# Sheet1.net
KiCad netlist of a schematic drawn in Altium Designer
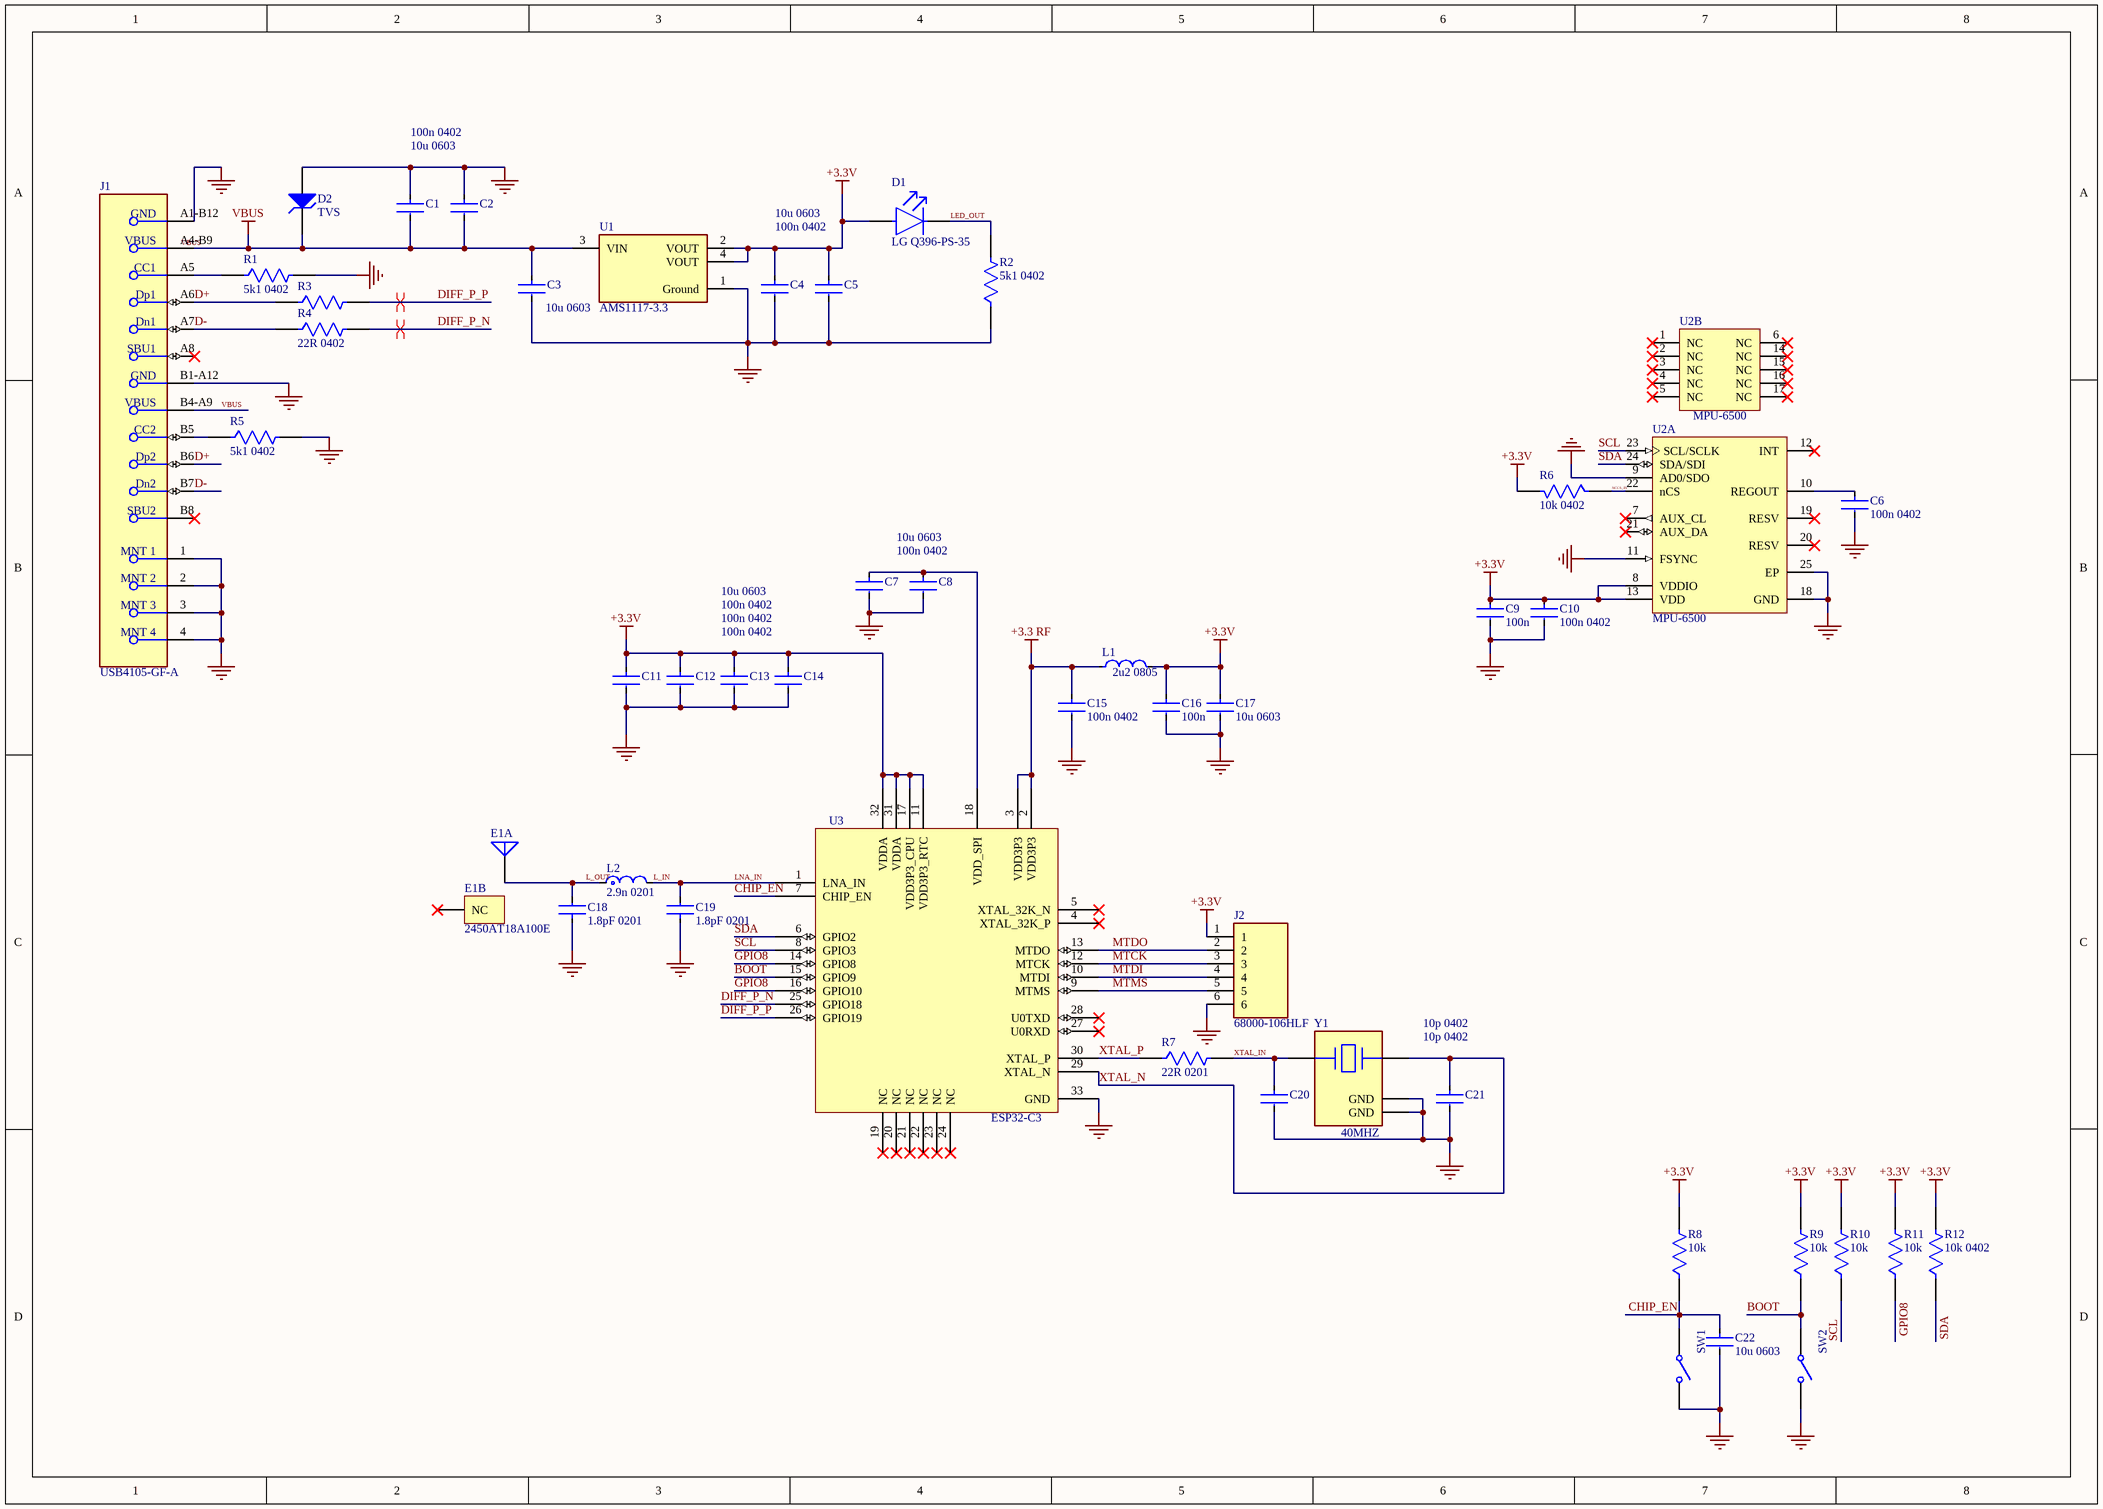
[diagram p0: Sheet1.SchDoc]

(export (version "E")
  (design (tool "Eeschema 10.0.6"))
  (components
    (comp (ref "C1")
      (value "100n 0402")
      (footprint "FP-0402B104K500CT-IPC_C")
      (description "CAP CER 0.1UF 50V X7R 0402")
      (fields (field (name "TOLERANCE") "10%"))
      (libsource (lib "Altium Content Vault") (part "11868f565c42a9108669ba33697ecf6"))
    )
    (comp (ref "C2")
      (value "10u 0603")
      (footprint "FP-GRM188-0_15-IPC_C")
      (description "Chip Multilayer Ceramic Capacitors for General Purpose, 0603, 10uF, X5R, 15%, 20%, 16V")
      (fields (field (name "TOLERANCE") "20%"))
      (libsource (lib "Altium Content Vault") (part "02cd4be3c70576c341d710602a673aa"))
    )
    (comp (ref "C3")
      (value "10u 0603")
      (footprint "FP-GRM188-0_15-IPC_C")
      (description "Chip Multilayer Ceramic Capacitors for General Purpose, 0603, 10uF, X5R, 15%, 20%, 16V")
      (fields (field (name "TOLERANCE") "20%"))
      (libsource (lib "Altium Content Vault") (part "02cd4be3c70576c341d710602a673aa"))
    )
    (comp (ref "C4")
      (value "10u 0603")
      (footprint "FP-GRM188-0_15-IPC_C")
      (description "Chip Multilayer Ceramic Capacitors for General Purpose, 0603, 10uF, X5R, 15%, 20%, 16V")
      (fields (field (name "TOLERANCE") "20%"))
      (libsource (lib "Altium Content Vault") (part "02cd4be3c70576c341d710602a673aa"))
    )
    (comp (ref "C5")
      (value "100n 0402")
      (footprint "FP-0402B104K500CT-IPC_C")
      (description "CAP CER 0.1UF 50V X7R 0402")
      (fields (field (name "TOLERANCE") "10%"))
      (libsource (lib "Altium Content Vault") (part "11868f565c42a9108669ba33697ecf6"))
    )
    (comp (ref "C6")
      (value "100n 0402")
      (footprint "FP-0402B104K500CT-IPC_C")
      (description "CAP CER 0.1UF 50V X7R 0402")
      (fields (field (name "TOLERANCE") "10%"))
      (libsource (lib "Altium Content Vault") (part "11868f565c42a9108669ba33697ecf6"))
    )
    (comp (ref "C7")
      (value "10u 0603")
      (footprint "FP-GRM188-0_15-IPC_C")
      (description "Chip Multilayer Ceramic Capacitors for General Purpose, 0603, 10uF, X5R, 15%, 20%, 16V")
      (fields (field (name "TOLERANCE") "20%"))
      (libsource (lib "Altium Content Vault") (part "02cd4be3c70576c341d710602a673aa"))
    )
    (comp (ref "C8")
      (value "100n 0402")
      (footprint "FP-0402B104K500CT-IPC_C")
      (description "CAP CER 0.1UF 50V X7R 0402")
      (fields (field (name "TOLERANCE") "10%"))
      (libsource (lib "Altium Content Vault") (part "11868f565c42a9108669ba33697ecf6"))
    )
    (comp (ref "C9")
      (value "100n")
      (footprint "FP-0402B104K500CT-IPC_C")
      (description "CAP CER 0.1UF 50V X7R 0402")
      (fields (field (name "TOLERANCE") "10%"))
      (libsource (lib "Altium Content Vault") (part "11868f565c42a9108669ba33697ecf6"))
    )
    (comp (ref "C10")
      (value "100n 0402")
      (footprint "FP-0402B104K500CT-IPC_C")
      (description "CAP CER 0.1UF 50V X7R 0402")
      (fields (field (name "TOLERANCE") "10%"))
      (libsource (lib "Altium Content Vault") (part "11868f565c42a9108669ba33697ecf6"))
    )
    (comp (ref "C11")
      (value "10u 0603")
      (footprint "FP-GRM188-0_15-IPC_C")
      (description "Chip Multilayer Ceramic Capacitors for General Purpose, 0603, 10uF, X5R, 15%, 20%, 16V")
      (fields (field (name "TOLERANCE") "20%"))
      (libsource (lib "Altium Content Vault") (part "02cd4be3c70576c341d710602a673aa"))
    )
    (comp (ref "C12")
      (value "100n 0402")
      (footprint "FP-0402B104K500CT-IPC_C")
      (description "CAP CER 0.1UF 50V X7R 0402")
      (fields (field (name "TOLERANCE") "10%"))
      (libsource (lib "Altium Content Vault") (part "11868f565c42a9108669ba33697ecf6"))
    )
    (comp (ref "C13")
      (value "100n 0402")
      (footprint "FP-0402B104K500CT-IPC_C")
      (description "CAP CER 0.1UF 50V X7R 0402")
      (fields (field (name "TOLERANCE") "10%"))
      (libsource (lib "Altium Content Vault") (part "11868f565c42a9108669ba33697ecf6"))
    )
    (comp (ref "C14")
      (value "100n 0402")
      (footprint "FP-0402B104K500CT-IPC_C")
      (description "CAP CER 0.1UF 50V X7R 0402")
      (fields (field (name "TOLERANCE") "10%"))
      (libsource (lib "Altium Content Vault") (part "11868f565c42a9108669ba33697ecf6"))
    )
    (comp (ref "C15")
      (value "100n 0402")
      (footprint "FP-0402B104K500CT-IPC_C")
      (description "CAP CER 0.1UF 50V X7R 0402")
      (fields (field (name "TOLERANCE") "10%"))
      (libsource (lib "Altium Content Vault") (part "11868f565c42a9108669ba33697ecf6"))
    )
    (comp (ref "C16")
      (value "100n")
      (footprint "FP-0402B104K500CT-IPC_C")
      (description "CAP CER 0.1UF 50V X7R 0402")
      (fields (field (name "TOLERANCE") "10%"))
      (libsource (lib "Altium Content Vault") (part "11868f565c42a9108669ba33697ecf6"))
    )
    (comp (ref "C17")
      (value "10u 0603")
      (footprint "FP-GRM188-0_15-IPC_C")
      (description "Chip Multilayer Ceramic Capacitors for General Purpose, 0603, 10uF, X5R, 15%, 20%, 16V")
      (fields (field (name "TOLERANCE") "20%"))
      (libsource (lib "Altium Content Vault") (part "02cd4be3c70576c341d710602a673aa"))
    )
    (comp (ref "C18")
      (value "1.8pF 0201")
      (footprint "FP-GRM033-0_03-IPC_B")
      (description "Chip Multilayer Ceramic Capacitors for General Purpose, 0201, 1.8pF, C0G, 30ppm/°C, 0.1pF, 50V")
      (libsource (lib "Altium Content Vault") (part "b4654b650e69147ec39a6b967a45e02"))
    )
    (comp (ref "C19")
      (value "1.8pF 0201")
      (footprint "FP-GRM033-0_03-IPC_B")
      (description "Chip Multilayer Ceramic Capacitors for General Purpose, 0201, 1.8pF, C0G, 30ppm/°C, 0.1pF, 50V")
      (libsource (lib "Altium Content Vault") (part "b4654b650e69147ec39a6b967a45e02"))
    )
    (comp (ref "C20")
      (value "10p 0402")
      (footprint "FP-C0402-BB-MFG")
      (description "CAP CER 10PF 16V NP0 0402")
      (fields
        (field (name "OCTOPART") "https://octopart.com/c0402c100j4gac7867-kemet-1500972")
        (field (name "MANUFACTURER PART NUMBER") "C0402C100J4GAC7867")
      )
      (libsource (lib "Altium Content Vault") (part "b4654b650e69147ec39a6b967a45e02"))
    )
    (comp (ref "C21")
      (value "10p 0402")
      (footprint "FP-C0402-BB-MFG")
      (description "CAP CER 10PF 16V NP0 0402")
      (fields
        (field (name "OCTOPART") "https://octopart.com/c0402c100j4gac7867-kemet-1500972")
        (field (name "MANUFACTURER PART NUMBER") "C0402C100J4GAC7867")
      )
      (libsource (lib "Altium Content Vault") (part "b4654b650e69147ec39a6b967a45e02"))
    )
    (comp (ref "C22")
      (value "10u 0603")
      (footprint "FP-GRM188-0_15-IPC_C")
      (description "Chip Multilayer Ceramic Capacitors for General Purpose, 0603, 10uF, X5R, 15%, 20%, 16V")
      (fields (field (name "TOLERANCE") "20%"))
      (libsource (lib "Altium Content Vault") (part "02cd4be3c70576c341d710602a673aa"))
    )
    (comp (ref "D1")
      (value "LG Q396-PS-35")
      (footprint "FP-LG_Q396-MFG")
      (description "LED GREEN DIFFUSED 0603 SMD")
      (libsource (lib "Altium Content Vault") (part "8706943c75ba83719d021d2fdc84c58"))
    )
    (comp (ref "D2")
      (value "TVS")
      (footprint "ONSC-SOD-523-2-502-01_V")
      (fields (field (name "MANUFACTURER") "On Semiconductor") (field (name "PARTNUMBER") "ESD5Z5.0T1G"))
      (libsource (lib "Altium Content Vault") (part "ONSC-K1A2-2"))
    )
    (comp (ref "E1")
      (value "2450AT18A100E")
      (footprint "JT-2450AT18A100-2_V")
      (description "Ceramic Antenna, 2.45 GHZ, 2 W, -40 to 125 degC, 2-Pin SMD, RoHS, Tape and Reel")
      (fields (field (name "MANUFACTURER") "Johanson Technology"))
      (libsource (lib "Altium Content Vault") (part "JT-2450AT18A100-2"))
    )
    (comp (ref "J1")
      (value "USB4105-GF-A")
      (footprint "FP-USB4105-GF-A-MFG")
      (description "CONN RCPT USB2.0 TYPEC 5A")
      (fields
        (field (name "MANUFACTURER") "GCT")
        (field (name "OCTOPART") "https://octopart.com/usb4105-gf-a-gct-106627878")
      )
      (libsource (lib "Schlib1") (part "e7c17a616881a82b79941196b4bec10"))
    )
    (comp (ref "J2")
      (value "68000-106HLF")
      (footprint "HDRV6W64P0X254_1X6_1524X254X839P")
      (description "Headers & Wire Housings 6POS HDR 30AU")
      (fields (field (name "MOUSER PART NUMBER") "649-68000-106HLF"))
      (libsource (lib "68000-106HLF") (part "68000-106HLF"))
    )
    (comp (ref "L1")
      (value "2u2 0805")
      (footprint "FP-MLZ2012-0_85-IPC_B")
      (description "Shielded Multilayer Inductor 2.2uH ±20% 800mA 156mΩ AEC-Q200 SMD 0805")
      (fields (field (name "TOLERANCE") "20%"))
      (libsource (lib "Altium Content Vault") (part "725321dda6339637d4d059423bc1c3c"))
    )
    (comp (ref "L2")
      (value "2.9n 0201")
      (footprint "FP-LQP03TG_02-IPC_B")
      (description "Film type RF Inductor 2.9nH ±0.1nH 500mA 0.2Ω 0201 (0603)")
      (libsource (lib "Altium Content Vault") (part "4cc4b267dca4c8e51f7102f422741d8"))
    )
    (comp (ref "R1")
      (value "5k1 0402")
      (footprint "FP-RN73R1E-IPC_C")
      (description "5.1kΩ ±1% 0.063W, 1/16W Chip Resistor 0402 (1005 Metric) Moisture Resistant Thin Film")
      (libsource (lib "Altium Content Vault") (part "1029c3af85768c4190bb7ad29bc67b5"))
    )
    (comp (ref "R2")
      (value "5k1 0402")
      (footprint "FP-RN73R1E-IPC_C")
      (description "5.1kΩ ±1% 0.063W, 1/16W Chip Resistor 0402 (1005 Metric) Moisture Resistant Thin Film")
      (libsource (lib "Altium Content Vault") (part "1029c3af85768c4190bb7ad29bc67b5"))
    )
    (comp (ref "R3")
      (value "22R 0402")
      (footprint "FP-MCR01-IPC_C")
      (description "Thick Film Chip Resistor, 0402, 22Ω, 1%, 100ppm/°C, 0.063W, 50V")
      (fields (field (name "TOLERANCE") "1%"))
      (libsource (lib "Altium Content Vault") (part "1029c3af85768c4190bb7ad29bc67b5"))
    )
    (comp (ref "R4")
      (value "22R 0402")
      (footprint "FP-MCR01-IPC_C")
      (description "Thick Film Chip Resistor, 0402, 22Ω, 1%, 100ppm/°C, 0.063W, 50V")
      (fields (field (name "TOLERANCE") "1%"))
      (libsource (lib "Altium Content Vault") (part "1029c3af85768c4190bb7ad29bc67b5"))
    )
    (comp (ref "R5")
      (value "5k1 0402")
      (footprint "FP-RN73R1E-IPC_C")
      (description "5.1kΩ ±1% 0.063W, 1/16W Chip Resistor 0402 (1005 Metric) Moisture Resistant Thin Film")
      (libsource (lib "Altium Content Vault") (part "1029c3af85768c4190bb7ad29bc67b5"))
    )
    (comp (ref "R6")
      (value "10k 0402")
      (footprint "FP-MCS0402-IPC_C")
      (description "RES SMD 1.2K OHM 1% 1/10W 0402")
      (fields (field (name "TOLERANCE") "0.1%"))
      (libsource (lib "Altium Content Vault") (part "1029c3af85768c4190bb7ad29bc67b5"))
    )
    (comp (ref "R7")
      (value "22R 0201")
      (footprint "FP-AF0201-IPC_A")
      (description "Anti-Sulfurated Chip Resistors Automotive Grade 22Ω 5% 200ppm/°C 0201")
      (fields (field (name "TOLERANCE") "5%"))
      (libsource (lib "Altium Content Vault") (part "1029c3af85768c4190bb7ad29bc67b5"))
    )
    (comp (ref "R8")
      (value "10k")
      (footprint "FP-MCS0402-IPC_C")
      (description "RES SMD 1.2K OHM 1% 1/10W 0402")
      (fields (field (name "TOLERANCE") "0.1%"))
      (libsource (lib "Altium Content Vault") (part "1029c3af85768c4190bb7ad29bc67b5"))
    )
    (comp (ref "R9")
      (value "10k")
      (footprint "FP-MCS0402-IPC_C")
      (description "RES SMD 1.2K OHM 1% 1/10W 0402")
      (fields (field (name "TOLERANCE") "0.1%"))
      (libsource (lib "Altium Content Vault") (part "1029c3af85768c4190bb7ad29bc67b5"))
    )
    (comp (ref "R10")
      (value "10k")
      (footprint "FP-MCS0402-IPC_C")
      (description "RES SMD 1.2K OHM 1% 1/10W 0402")
      (fields (field (name "TOLERANCE") "0.1%"))
      (libsource (lib "Altium Content Vault") (part "1029c3af85768c4190bb7ad29bc67b5"))
    )
    (comp (ref "R11")
      (value "10k")
      (footprint "FP-MCS0402-IPC_C")
      (description "RES SMD 1.2K OHM 1% 1/10W 0402")
      (fields (field (name "TOLERANCE") "0.1%"))
      (libsource (lib "Altium Content Vault") (part "1029c3af85768c4190bb7ad29bc67b5"))
    )
    (comp (ref "R12")
      (value "10k 0402")
      (footprint "FP-MCS0402-IPC_C")
      (description "RES SMD 1.2K OHM 1% 1/10W 0402")
      (fields (field (name "TOLERANCE") "0.1%"))
      (libsource (lib "Altium Content Vault") (part "1029c3af85768c4190bb7ad29bc67b5"))
    )
    (comp (ref "SW1")
      (value "434121025816")
      (footprint "434121025816")
      (description "Switch Tactile Spst-no 0.05A 12V")
      (libsource (lib "Altium Content Vault") (part "SPST-NO_2P"))
    )
    (comp (ref "SW2")
      (value "434121025816")
      (footprint "434121025816")
      (description "Switch Tactile Spst-no 0.05A 12V")
      (libsource (lib "Altium Content Vault") (part "SPST-NO_2P"))
    )
    (comp (ref "U1")
      (value "AMS1117-3.3")
      (footprint "FP-AMS1117-IPC_C")
      (description "LDO Voltage Regulators 1A, 3.3V")
      (fields
        (field (name "OCTOPART") "https://octopart.com/ams1117-3.3-advanced+monolithic+systems-25899300")
        (field (name "MANUFACTURER") "Advanced Monolithic Systems")
      )
      (libsource (lib "Altium Content Vault") (part "8bdbb5f8e77002000e30dd2845d0354"))
    )
    (comp (ref "U2")
      (value "MPU-6500")
      (footprint "INSE-MPU-6500-QFN24_M")
      (fields (field (name "MANUFACTURER") "InvenSense"))
      (libsource (lib "Altium Content Vault") (part "INSE-MPU-6500-24"))
    )
    (comp (ref "U3")
      (value "ESP32-C3")
      (footprint "ESP32-C3 - duplicate2")
      (description "RISC-V MCU with Wi-Fi and BLE")
      (fields (field (name "MANUFACTURER") "Espressif Systems"))
      (libsource (lib "Schlib1") (part "ESP32-C3"))
    )
    (comp (ref "Y1")
      (value "40MHZ")
      (footprint "FP-ABM3B-MFG")
      (description "Crystal 19.44MHz ±10ppm 10pF SMD-4 5mm x 3.2mm")
      (fields (field (name "TOLERANCE") "10ppm"))
      (libsource (lib "Altium Content Vault") (part "48e526d86b7f2615d98721063c72f49"))
    )
  )
  (nets
    (net (code "1") (name "+3.3 RF") (class "Default")
      (node (ref "C15") (pin "1") (pinfunction "1_1") (pintype "passive"))
      (node (ref "L1") (pin "1") (pinfunction "1_1") (pintype "passive"))
      (node (ref "U3") (pin "2") (pinfunction "VDD3P3_2") (pintype "power_in"))
      (node (ref "U3") (pin "3") (pinfunction "VDD3P3_3") (pintype "power_in"))
    )
    (net (code "2") (name "+3.3V") (class "Default")
      (node (ref "C10") (pin "1") (pinfunction "1_1") (pintype "passive"))
      (node (ref "C11") (pin "1") (pinfunction "1_1") (pintype "passive"))
      (node (ref "C12") (pin "1") (pinfunction "1_1") (pintype "passive"))
      (node (ref "C13") (pin "1") (pinfunction "1_1") (pintype "passive"))
      (node (ref "C14") (pin "1") (pinfunction "1_1") (pintype "passive"))
      (node (ref "C16") (pin "1") (pinfunction "1_1") (pintype "passive"))
      (node (ref "C17") (pin "1") (pinfunction "1_1") (pintype "passive"))
      (node (ref "C4") (pin "1") (pinfunction "1_1") (pintype "passive"))
      (node (ref "C5") (pin "1") (pinfunction "1_1") (pintype "passive"))
      (node (ref "C9") (pin "1") (pinfunction "1_1") (pintype "passive"))
      (node (ref "D1") (pin "2") (pinfunction "A_2") (pintype "passive"))
      (node (ref "J2") (pin "1") (pinfunction "1_1") (pintype "passive"))
      (node (ref "L1") (pin "2") (pinfunction "2_2") (pintype "passive"))
      (node (ref "R10") (pin "2") (pinfunction "2_2") (pintype "passive"))
      (node (ref "R11") (pin "2") (pinfunction "2_2") (pintype "passive"))
      (node (ref "R12") (pin "2") (pinfunction "2_2") (pintype "passive"))
      (node (ref "R6") (pin "2") (pinfunction "2_2") (pintype "passive"))
      (node (ref "R8") (pin "2") (pinfunction "2_2") (pintype "passive"))
      (node (ref "R9") (pin "2") (pinfunction "2_2") (pintype "passive"))
      (node (ref "U1") (pin "2") (pinfunction "VOUT_2") (pintype "passive"))
      (node (ref "U1") (pin "4") (pinfunction "VOUT_4") (pintype "passive"))
      (node (ref "U2") (pin "13") (pinfunction "VDD_13") (pintype "power_in"))
      (node (ref "U2") (pin "8") (pinfunction "VDDIO_8") (pintype "power_in"))
      (node (ref "U3") (pin "11") (pinfunction "VDD3P3_RTC_11") (pintype "power_in"))
      (node (ref "U3") (pin "17") (pinfunction "VDD3P3_CPU_17") (pintype "power_in"))
      (node (ref "U3") (pin "31") (pinfunction "VDDA_31") (pintype "power_in"))
      (node (ref "U3") (pin "32") (pinfunction "VDDA_32") (pintype "power_in"))
    )
    (net (code "3") (name "/BOOT") (class "Default")
      (node (ref "R9") (pin "1") (pinfunction "1_1") (pintype "passive"))
      (node (ref "SW2") (pin "1") (pinfunction "1_1") (pintype "passive"))
      (node (ref "U3") (pin "15") (pinfunction "GPIO9_15") (pintype "bidirectional"))
    )
    (net (code "4") (name "/CHIP_EN") (class "Default")
      (node (ref "C22") (pin "1") (pinfunction "1_1") (pintype "passive"))
      (node (ref "R8") (pin "1") (pinfunction "1_1") (pintype "passive"))
      (node (ref "SW1") (pin "1") (pinfunction "1_1") (pintype "passive"))
      (node (ref "U3") (pin "7") (pinfunction "CHIP_EN_7") (pintype "passive"))
    )
    (net (code "5") (name "/D+") (class "Default")
      (node (ref "J1") (pin "A6") (pinfunction "Dp1_A6") (pintype "bidirectional"))
      (node (ref "J1") (pin "B6") (pinfunction "Dp2_B6") (pintype "bidirectional"))
      (node (ref "R3") (pin "1") (pinfunction "1_1") (pintype "passive"))
    )
    (net (code "6") (name "/D-") (class "Default")
      (node (ref "J1") (pin "A7") (pinfunction "Dn1_A7") (pintype "bidirectional"))
      (node (ref "J1") (pin "B7") (pinfunction "Dn2_B7") (pintype "bidirectional"))
      (node (ref "R4") (pin "1") (pinfunction "1_1") (pintype "passive"))
    )
    (net (code "7") (name "/DIFF_P_N") (class "Default")
      (node (ref "R4") (pin "2") (pinfunction "2_2") (pintype "passive"))
      (node (ref "U3") (pin "25") (pinfunction "GPIO18_25") (pintype "bidirectional"))
    )
    (net (code "8") (name "/DIFF_P_P") (class "Default")
      (node (ref "R3") (pin "2") (pinfunction "2_2") (pintype "passive"))
      (node (ref "U3") (pin "26") (pinfunction "GPIO19_26") (pintype "bidirectional"))
    )
    (net (code "9") (name "/GPIO8") (class "Default")
      (node (ref "R11") (pin "1") (pinfunction "1_1") (pintype "passive"))
      (node (ref "U3") (pin "14") (pinfunction "GPIO8_14") (pintype "bidirectional"))
      (node (ref "U3") (pin "16") (pinfunction "GPIO10_16") (pintype "bidirectional"))
    )
    (net (code "10") (name "/LED_OUT") (class "Default")
      (node (ref "D1") (pin "1") (pinfunction "C_1") (pintype "passive"))
      (node (ref "R2") (pin "2") (pinfunction "2_2") (pintype "passive"))
    )
    (net (code "11") (name "/LNA_IN") (class "Default")
      (node (ref "C19") (pin "2") (pinfunction "2_2") (pintype "passive"))
      (node (ref "L2") (pin "2") (pinfunction "2_2") (pintype "passive"))
      (node (ref "U3") (pin "1") (pinfunction "LNA_IN_1") (pintype "passive"))
    )
    (net (code "12") (name "/L_OUT") (class "Default")
      (node (ref "C18") (pin "2") (pinfunction "2_2") (pintype "passive"))
      (node (ref "E1") (pin "1") (pinfunction "FP_1") (pintype "passive"))
      (node (ref "L2") (pin "1") (pinfunction "1_1") (pintype "passive"))
    )
    (net (code "13") (name "/MTCK") (class "Default")
      (node (ref "J2") (pin "3") (pinfunction "3_3") (pintype "passive"))
      (node (ref "U3") (pin "12") (pinfunction "MTCK_12") (pintype "bidirectional"))
    )
    (net (code "14") (name "/MTDI") (class "Default")
      (node (ref "J2") (pin "4") (pinfunction "4_4") (pintype "passive"))
      (node (ref "U3") (pin "10") (pinfunction "MTDI_10") (pintype "bidirectional"))
    )
    (net (code "15") (name "/MTDO") (class "Default")
      (node (ref "J2") (pin "2") (pinfunction "2_2") (pintype "passive"))
      (node (ref "U3") (pin "13") (pinfunction "MTDO_13") (pintype "bidirectional"))
    )
    (net (code "16") (name "/MTMS") (class "Default")
      (node (ref "J2") (pin "5") (pinfunction "5_5") (pintype "passive"))
      (node (ref "U3") (pin "9") (pinfunction "MTMS_9") (pintype "bidirectional"))
    )
    (net (code "17") (name "/NCCS_IN") (class "Default")
      (node (ref "R6") (pin "1") (pinfunction "1_1") (pintype "passive"))
      (node (ref "U2") (pin "22") (pinfunction "nCS_22") (pintype "passive"))
    )
    (net (code "18") (name "/SCL") (class "Default")
      (node (ref "R10") (pin "1") (pinfunction "1_1") (pintype "passive"))
      (node (ref "U2") (pin "23") (pinfunction "SCL/SCLK_23") (pintype "input"))
      (node (ref "U3") (pin "8") (pinfunction "GPIO3_8") (pintype "bidirectional"))
    )
    (net (code "19") (name "/SDA") (class "Default")
      (node (ref "R12") (pin "1") (pinfunction "1_1") (pintype "passive"))
      (node (ref "U2") (pin "24") (pinfunction "SDA/SDI_24") (pintype "bidirectional"))
      (node (ref "U3") (pin "6") (pinfunction "GPIO2_6") (pintype "bidirectional"))
    )
    (net (code "20") (name "/XTAL_IN") (class "Default")
      (node (ref "C20") (pin "1") (pinfunction "1_1") (pintype "passive"))
      (node (ref "R7") (pin "2") (pinfunction "2_2") (pintype "passive"))
      (node (ref "Y1") (pin "1") (pinfunction "1_1") (pintype "passive"))
    )
    (net (code "21") (name "/XTAL_N") (class "Default")
      (node (ref "C21") (pin "1") (pinfunction "1_1") (pintype "passive"))
      (node (ref "U3") (pin "29") (pinfunction "XTAL_N_29") (pintype "passive"))
      (node (ref "Y1") (pin "3") (pinfunction "3_3") (pintype "passive"))
    )
    (net (code "22") (name "/XTAL_P") (class "Default")
      (node (ref "R7") (pin "1") (pinfunction "1_1") (pintype "passive"))
      (node (ref "U3") (pin "30") (pinfunction "XTAL_P_30") (pintype "passive"))
    )
    (net (code "23") (name "GND") (class "Default")
      (node (ref "C1") (pin "1") (pinfunction "1_1") (pintype "passive"))
      (node (ref "C10") (pin "2") (pinfunction "2_2") (pintype "passive"))
      (node (ref "C11") (pin "2") (pinfunction "2_2") (pintype "passive"))
      (node (ref "C12") (pin "2") (pinfunction "2_2") (pintype "passive"))
      (node (ref "C13") (pin "2") (pinfunction "2_2") (pintype "passive"))
      (node (ref "C14") (pin "2") (pinfunction "2_2") (pintype "passive"))
      (node (ref "C15") (pin "2") (pinfunction "2_2") (pintype "passive"))
      (node (ref "C16") (pin "2") (pinfunction "2_2") (pintype "passive"))
      (node (ref "C17") (pin "2") (pinfunction "2_2") (pintype "passive"))
      (node (ref "C18") (pin "1") (pinfunction "1_1") (pintype "passive"))
      (node (ref "C19") (pin "1") (pinfunction "1_1") (pintype "passive"))
      (node (ref "C2") (pin "1") (pinfunction "1_1") (pintype "passive"))
      (node (ref "C20") (pin "2") (pinfunction "2_2") (pintype "passive"))
      (node (ref "C21") (pin "2") (pinfunction "2_2") (pintype "passive"))
      (node (ref "C22") (pin "2") (pinfunction "2_2") (pintype "passive"))
      (node (ref "C3") (pin "2") (pinfunction "2_2") (pintype "passive"))
      (node (ref "C4") (pin "2") (pinfunction "2_2") (pintype "passive"))
      (node (ref "C5") (pin "2") (pinfunction "2_2") (pintype "passive"))
      (node (ref "C6") (pin "2") (pinfunction "2_2") (pintype "passive"))
      (node (ref "C7") (pin "2") (pinfunction "2_2") (pintype "passive"))
      (node (ref "C8") (pin "2") (pinfunction "2_2") (pintype "passive"))
      (node (ref "C9") (pin "2") (pinfunction "2_2") (pintype "passive"))
      (node (ref "D2") (pin "2") (pinfunction "A_2") (pintype "passive"))
      (node (ref "J1") (pin "1") (pinfunction "MNT_1_1") (pintype "passive"))
      (node (ref "J1") (pin "2") (pinfunction "MNT_2_2") (pintype "passive"))
      (node (ref "J1") (pin "3") (pinfunction "MNT_3_3") (pintype "passive"))
      (node (ref "J1") (pin "4") (pinfunction "MNT_4_4") (pintype "passive"))
      (node (ref "J1") (pin "A1-B12") (pinfunction "GND_A1-B12") (pintype "passive"))
      (node (ref "J1") (pin "B1-A12") (pinfunction "GND_B1-A12") (pintype "passive"))
      (node (ref "J2") (pin "6") (pinfunction "6_6") (pintype "passive"))
      (node (ref "R1") (pin "2") (pinfunction "2_2") (pintype "passive"))
      (node (ref "R2") (pin "1") (pinfunction "1_1") (pintype "passive"))
      (node (ref "R5") (pin "2") (pinfunction "2_2") (pintype "passive"))
      (node (ref "SW1") (pin "2") (pinfunction "2_2") (pintype "passive"))
      (node (ref "SW2") (pin "2") (pinfunction "2_2") (pintype "passive"))
      (node (ref "U1") (pin "1") (pinfunction "Ground_1") (pintype "passive"))
      (node (ref "U2") (pin "11") (pinfunction "FSYNC_11") (pintype "input"))
      (node (ref "U2") (pin "18") (pinfunction "GND_18") (pintype "passive"))
      (node (ref "U2") (pin "25") (pinfunction "EP_25") (pintype "passive"))
      (node (ref "U2") (pin "9") (pinfunction "AD0/SDO_9") (pintype "passive"))
      (node (ref "U3") (pin "33") (pinfunction "GND_33") (pintype "passive"))
      (node (ref "Y1") (pin "2") (pinfunction "GND_2") (pintype "passive"))
      (node (ref "Y1") (pin "4") (pinfunction "GND_4") (pintype "passive"))
    )
    (net (code "24") (name "Net-(J1-CC1)") (class "Default")
      (node (ref "J1") (pin "A5") (pinfunction "CC1_A5") (pintype "power_in"))
      (node (ref "R1") (pin "1") (pinfunction "1_1") (pintype "passive"))
    )
    (net (code "25") (name "Net-(J1-CC2)") (class "Default")
      (node (ref "J1") (pin "B5") (pinfunction "CC2_B5") (pintype "bidirectional"))
      (node (ref "R5") (pin "1") (pinfunction "1_1") (pintype "passive"))
    )
    (net (code "26") (name "Net-(U2A-REGOUT)") (class "Default")
      (node (ref "C6") (pin "1") (pinfunction "1_1") (pintype "passive"))
      (node (ref "U2") (pin "10") (pinfunction "REGOUT_10") (pintype "passive"))
    )
    (net (code "27") (name "Net-(U3-VDD_SPI)") (class "Default")
      (node (ref "C7") (pin "1") (pinfunction "1_1") (pintype "passive"))
      (node (ref "C8") (pin "1") (pinfunction "1_1") (pintype "passive"))
      (node (ref "U3") (pin "18") (pinfunction "VDD_SPI_18") (pintype "power_in"))
    )
    (net (code "28") (name "VBUS") (class "Default")
      (node (ref "C1") (pin "2") (pinfunction "2_2") (pintype "passive"))
      (node (ref "C2") (pin "2") (pinfunction "2_2") (pintype "passive"))
      (node (ref "C3") (pin "1") (pinfunction "1_1") (pintype "passive"))
      (node (ref "D2") (pin "1") (pinfunction "K_1") (pintype "passive"))
      (node (ref "J1") (pin "A4-B9") (pinfunction "VBUS_A4-B9") (pintype "power_in"))
      (node (ref "J1") (pin "B4-A9") (pinfunction "VBUS_B4-A9") (pintype "power_in"))
      (node (ref "U1") (pin "3") (pinfunction "VIN_3") (pintype "power_in"))
    )
    (net (code "29") (name "unconnected-(E1B-NC-Pad2)") (class "Default")
      (node (ref "E1") (pin "2") (pinfunction "NC_2") (pintype "passive+no_connect"))
    )
    (net (code "30") (name "unconnected-(J1-SBU1-PadA8)") (class "Default")
      (node (ref "J1") (pin "A8") (pinfunction "SBU1_A8") (pintype "bidirectional+no_connect"))
    )
    (net (code "31") (name "unconnected-(J1-SBU2-PadB8)") (class "Default")
      (node (ref "J1") (pin "B8") (pinfunction "SBU2_B8") (pintype "power_in+no_connect"))
    )
    (net (code "32") (name "unconnected-(U2A-AUX_CL-Pad7)") (class "Default")
      (node (ref "U2") (pin "7") (pinfunction "AUX_CL_7") (pintype "output+no_connect"))
    )
    (net (code "33") (name "unconnected-(U2A-AUX_DA-Pad21)") (class "Default")
      (node (ref "U2") (pin "21") (pinfunction "AUX_DA_21") (pintype "bidirectional+no_connect"))
    )
    (net (code "34") (name "unconnected-(U2A-INT-Pad12)") (class "Default")
      (node (ref "U2") (pin "12") (pinfunction "INT_12") (pintype "open_collector+no_connect"))
    )
    (net (code "35") (name "unconnected-(U2A-RESV-Pad19)") (class "Default")
      (node (ref "U2") (pin "19") (pinfunction "RESV_19") (pintype "passive+no_connect"))
    )
    (net (code "36") (name "unconnected-(U2A-RESV-Pad20)") (class "Default")
      (node (ref "U2") (pin "20") (pinfunction "RESV_20") (pintype "power_in+no_connect"))
    )
    (net (code "37") (name "unconnected-(U2B-NC-Pad1)") (class "Default")
      (node (ref "U2") (pin "1") (pinfunction "NC_1") (pintype "passive+no_connect"))
    )
    (net (code "38") (name "unconnected-(U2B-NC-Pad2)") (class "Default")
      (node (ref "U2") (pin "2") (pinfunction "NC_2") (pintype "passive+no_connect"))
    )
    (net (code "39") (name "unconnected-(U2B-NC-Pad3)") (class "Default")
      (node (ref "U2") (pin "3") (pinfunction "NC_3") (pintype "passive+no_connect"))
    )
    (net (code "40") (name "unconnected-(U2B-NC-Pad4)") (class "Default")
      (node (ref "U2") (pin "4") (pinfunction "NC_4") (pintype "passive+no_connect"))
    )
    (net (code "41") (name "unconnected-(U2B-NC-Pad5)") (class "Default")
      (node (ref "U2") (pin "5") (pinfunction "NC_5") (pintype "passive+no_connect"))
    )
    (net (code "42") (name "unconnected-(U2B-NC-Pad6)") (class "Default")
      (node (ref "U2") (pin "6") (pinfunction "NC_6") (pintype "passive+no_connect"))
    )
    (net (code "43") (name "unconnected-(U2B-NC-Pad14)") (class "Default")
      (node (ref "U2") (pin "14") (pinfunction "NC_14") (pintype "passive+no_connect"))
    )
    (net (code "44") (name "unconnected-(U2B-NC-Pad15)") (class "Default")
      (node (ref "U2") (pin "15") (pinfunction "NC_15") (pintype "passive+no_connect"))
    )
    (net (code "45") (name "unconnected-(U2B-NC-Pad16)") (class "Default")
      (node (ref "U2") (pin "16") (pinfunction "NC_16") (pintype "passive+no_connect"))
    )
    (net (code "46") (name "unconnected-(U2B-NC-Pad17)") (class "Default")
      (node (ref "U2") (pin "17") (pinfunction "NC_17") (pintype "passive+no_connect"))
    )
    (net (code "47") (name "unconnected-(U3-NC-Pad19)") (class "Default")
      (node (ref "U3") (pin "19") (pinfunction "NC_19") (pintype "passive+no_connect"))
    )
    (net (code "48") (name "unconnected-(U3-NC-Pad20)") (class "Default")
      (node (ref "U3") (pin "20") (pinfunction "NC_20") (pintype "passive+no_connect"))
    )
    (net (code "49") (name "unconnected-(U3-NC-Pad21)") (class "Default")
      (node (ref "U3") (pin "21") (pinfunction "NC_21") (pintype "passive+no_connect"))
    )
    (net (code "50") (name "unconnected-(U3-NC-Pad22)") (class "Default")
      (node (ref "U3") (pin "22") (pinfunction "NC_22") (pintype "passive+no_connect"))
    )
    (net (code "51") (name "unconnected-(U3-NC-Pad23)") (class "Default")
      (node (ref "U3") (pin "23") (pinfunction "NC_23") (pintype "passive+no_connect"))
    )
    (net (code "52") (name "unconnected-(U3-NC-Pad24)") (class "Default")
      (node (ref "U3") (pin "24") (pinfunction "NC_24") (pintype "passive+no_connect"))
    )
    (net (code "53") (name "unconnected-(U3-U0RXD-Pad27)") (class "Default")
      (node (ref "U3") (pin "27") (pinfunction "U0RXD_27") (pintype "bidirectional+no_connect"))
    )
    (net (code "54") (name "unconnected-(U3-U0TXD-Pad28)") (class "Default")
      (node (ref "U3") (pin "28") (pinfunction "U0TXD_28") (pintype "bidirectional+no_connect"))
    )
    (net (code "55") (name "unconnected-(U3-XTAL_32K_N-Pad5)") (class "Default")
      (node (ref "U3") (pin "5") (pinfunction "XTAL_32K_N_5") (pintype "passive+no_connect"))
    )
    (net (code "56") (name "unconnected-(U3-XTAL_32K_P-Pad4)") (class "Default")
      (node (ref "U3") (pin "4") (pinfunction "XTAL_32K_P_4") (pintype "passive+no_connect"))
    )
  )
)
